# SolenoidX13.net
KiCad netlist of a schematic drawn in EAGLE
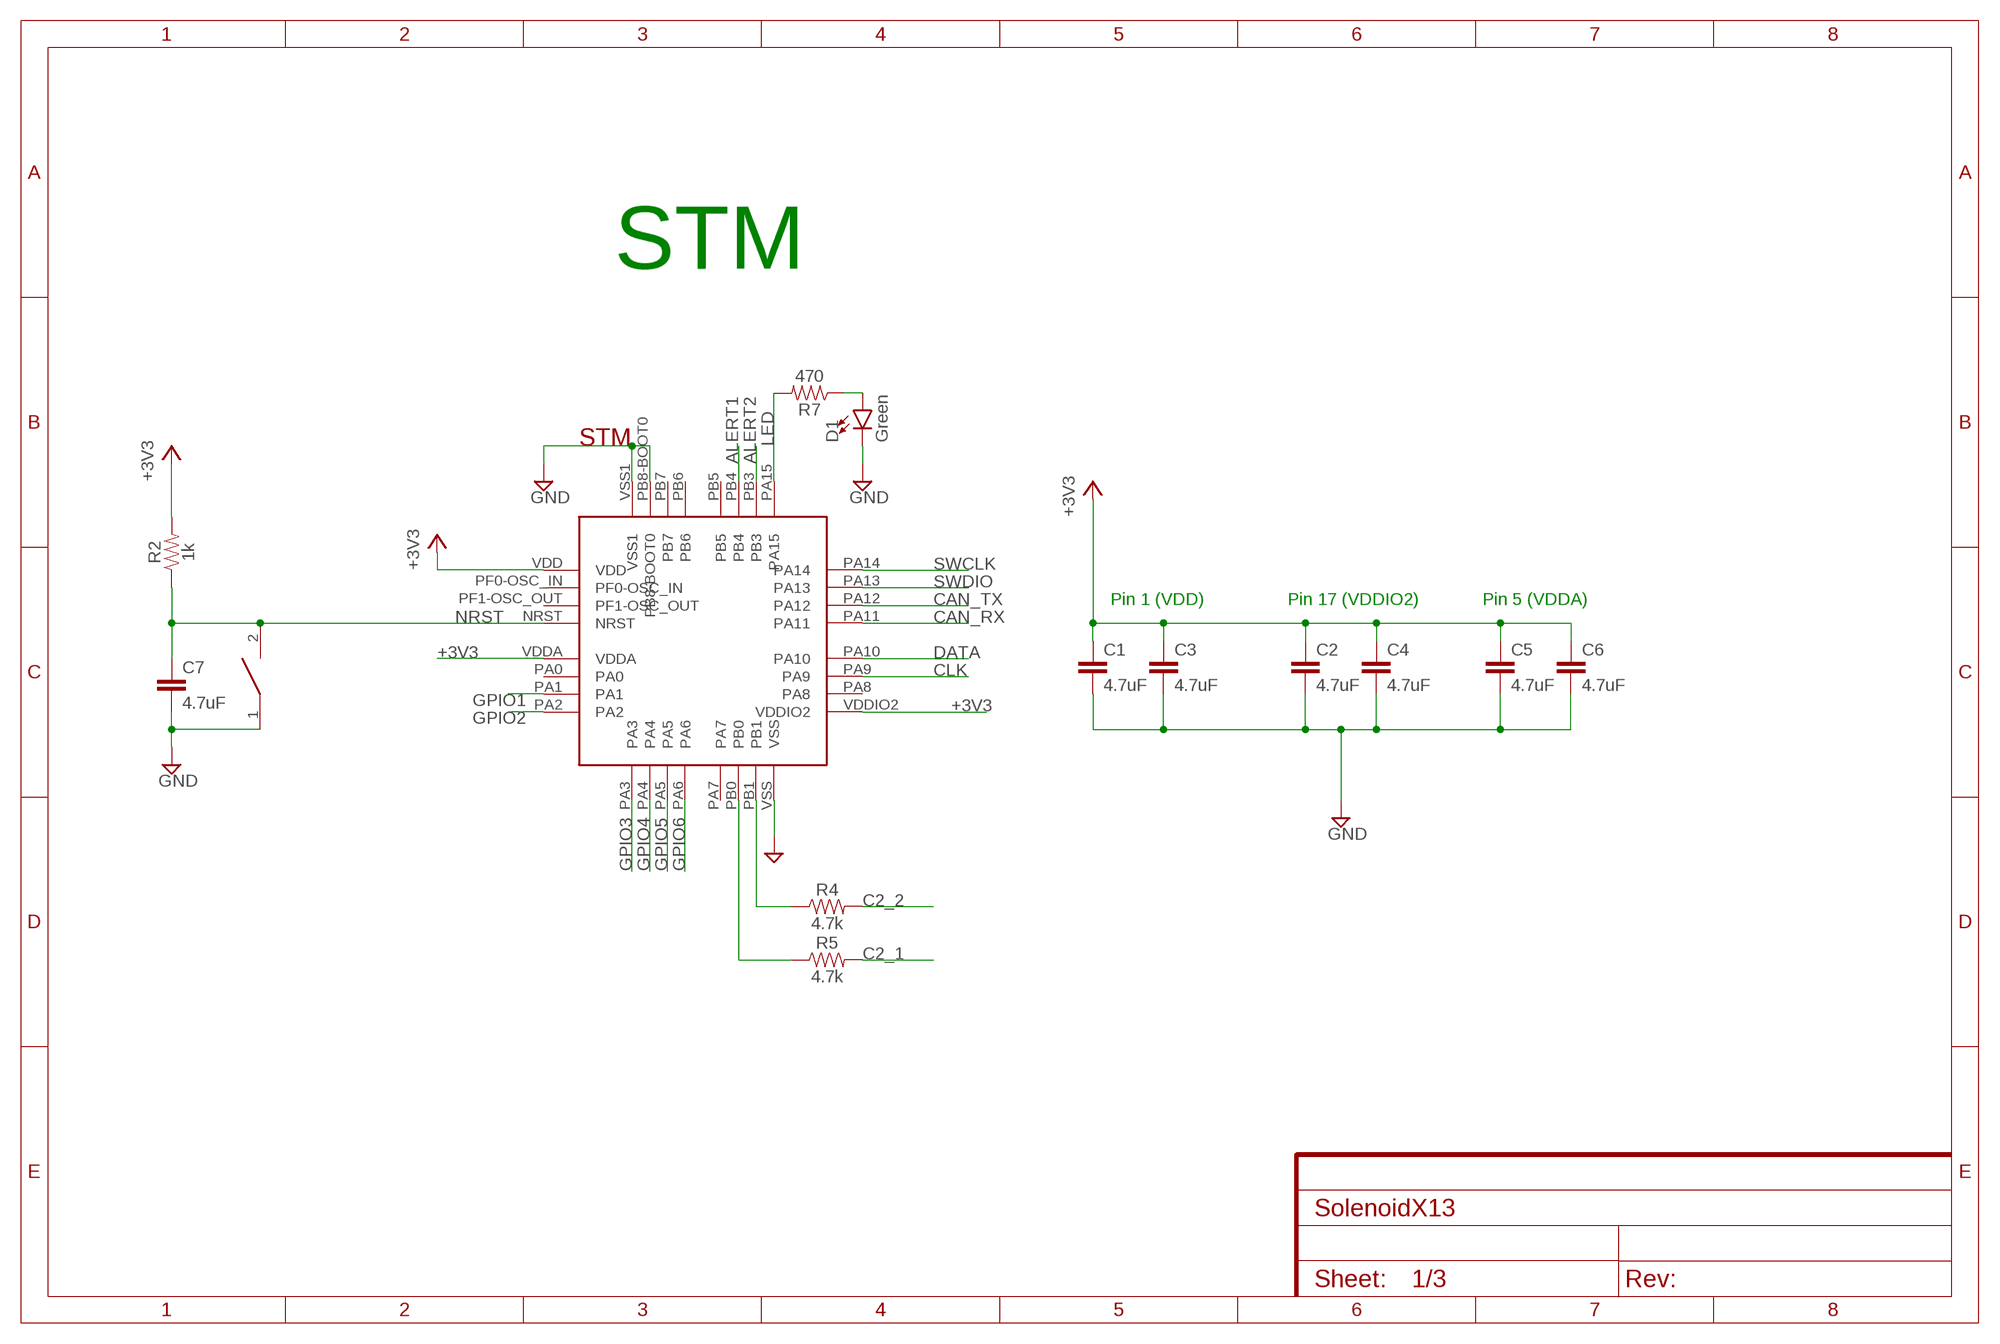
[diagram p0: schematic, sheet 1]
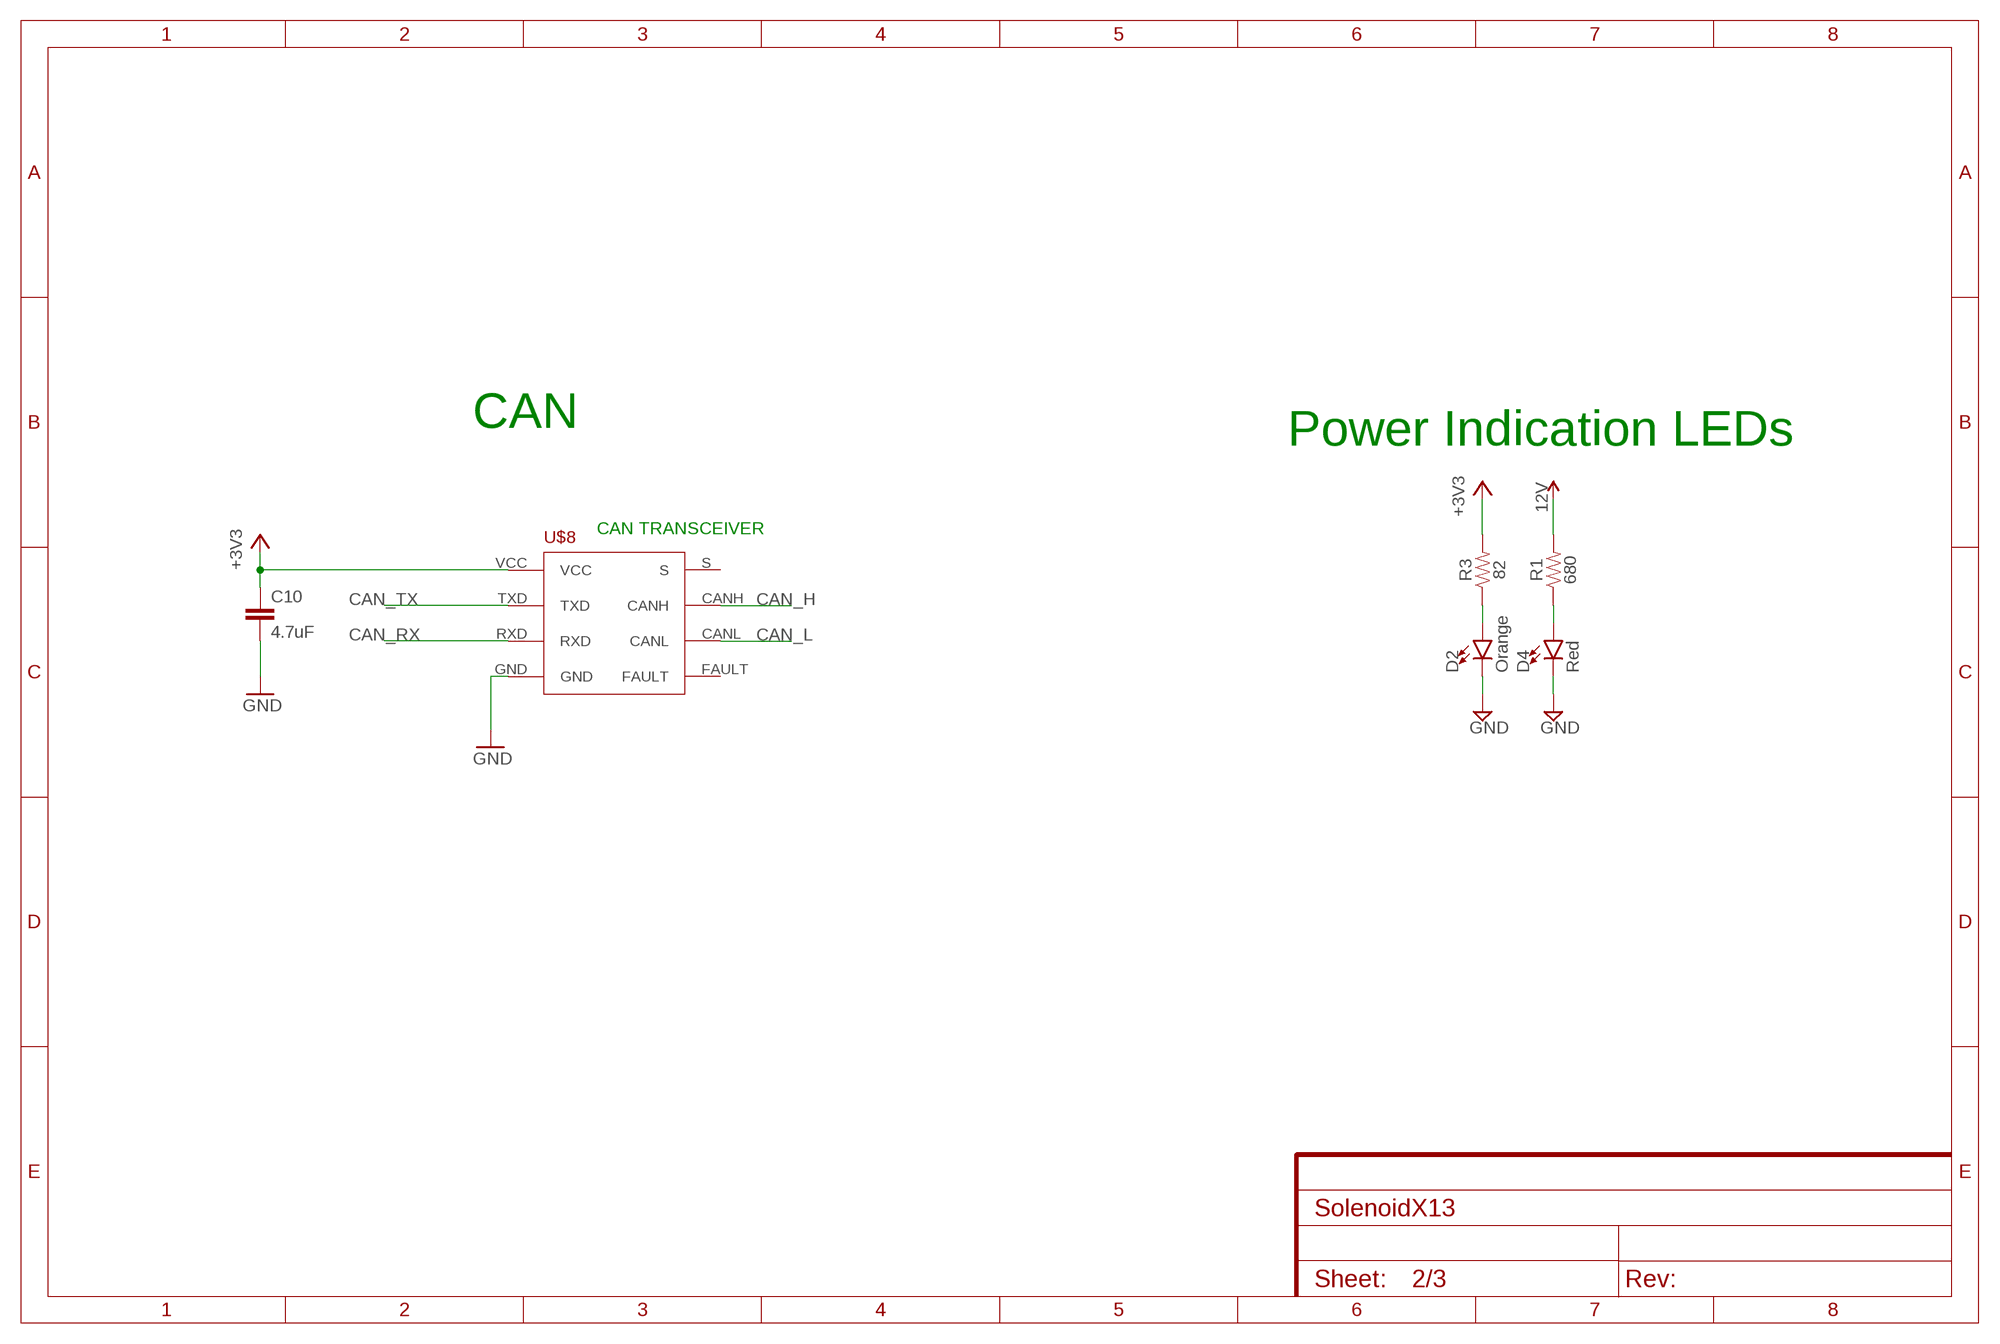
[diagram p1: schematic, sheet 2]
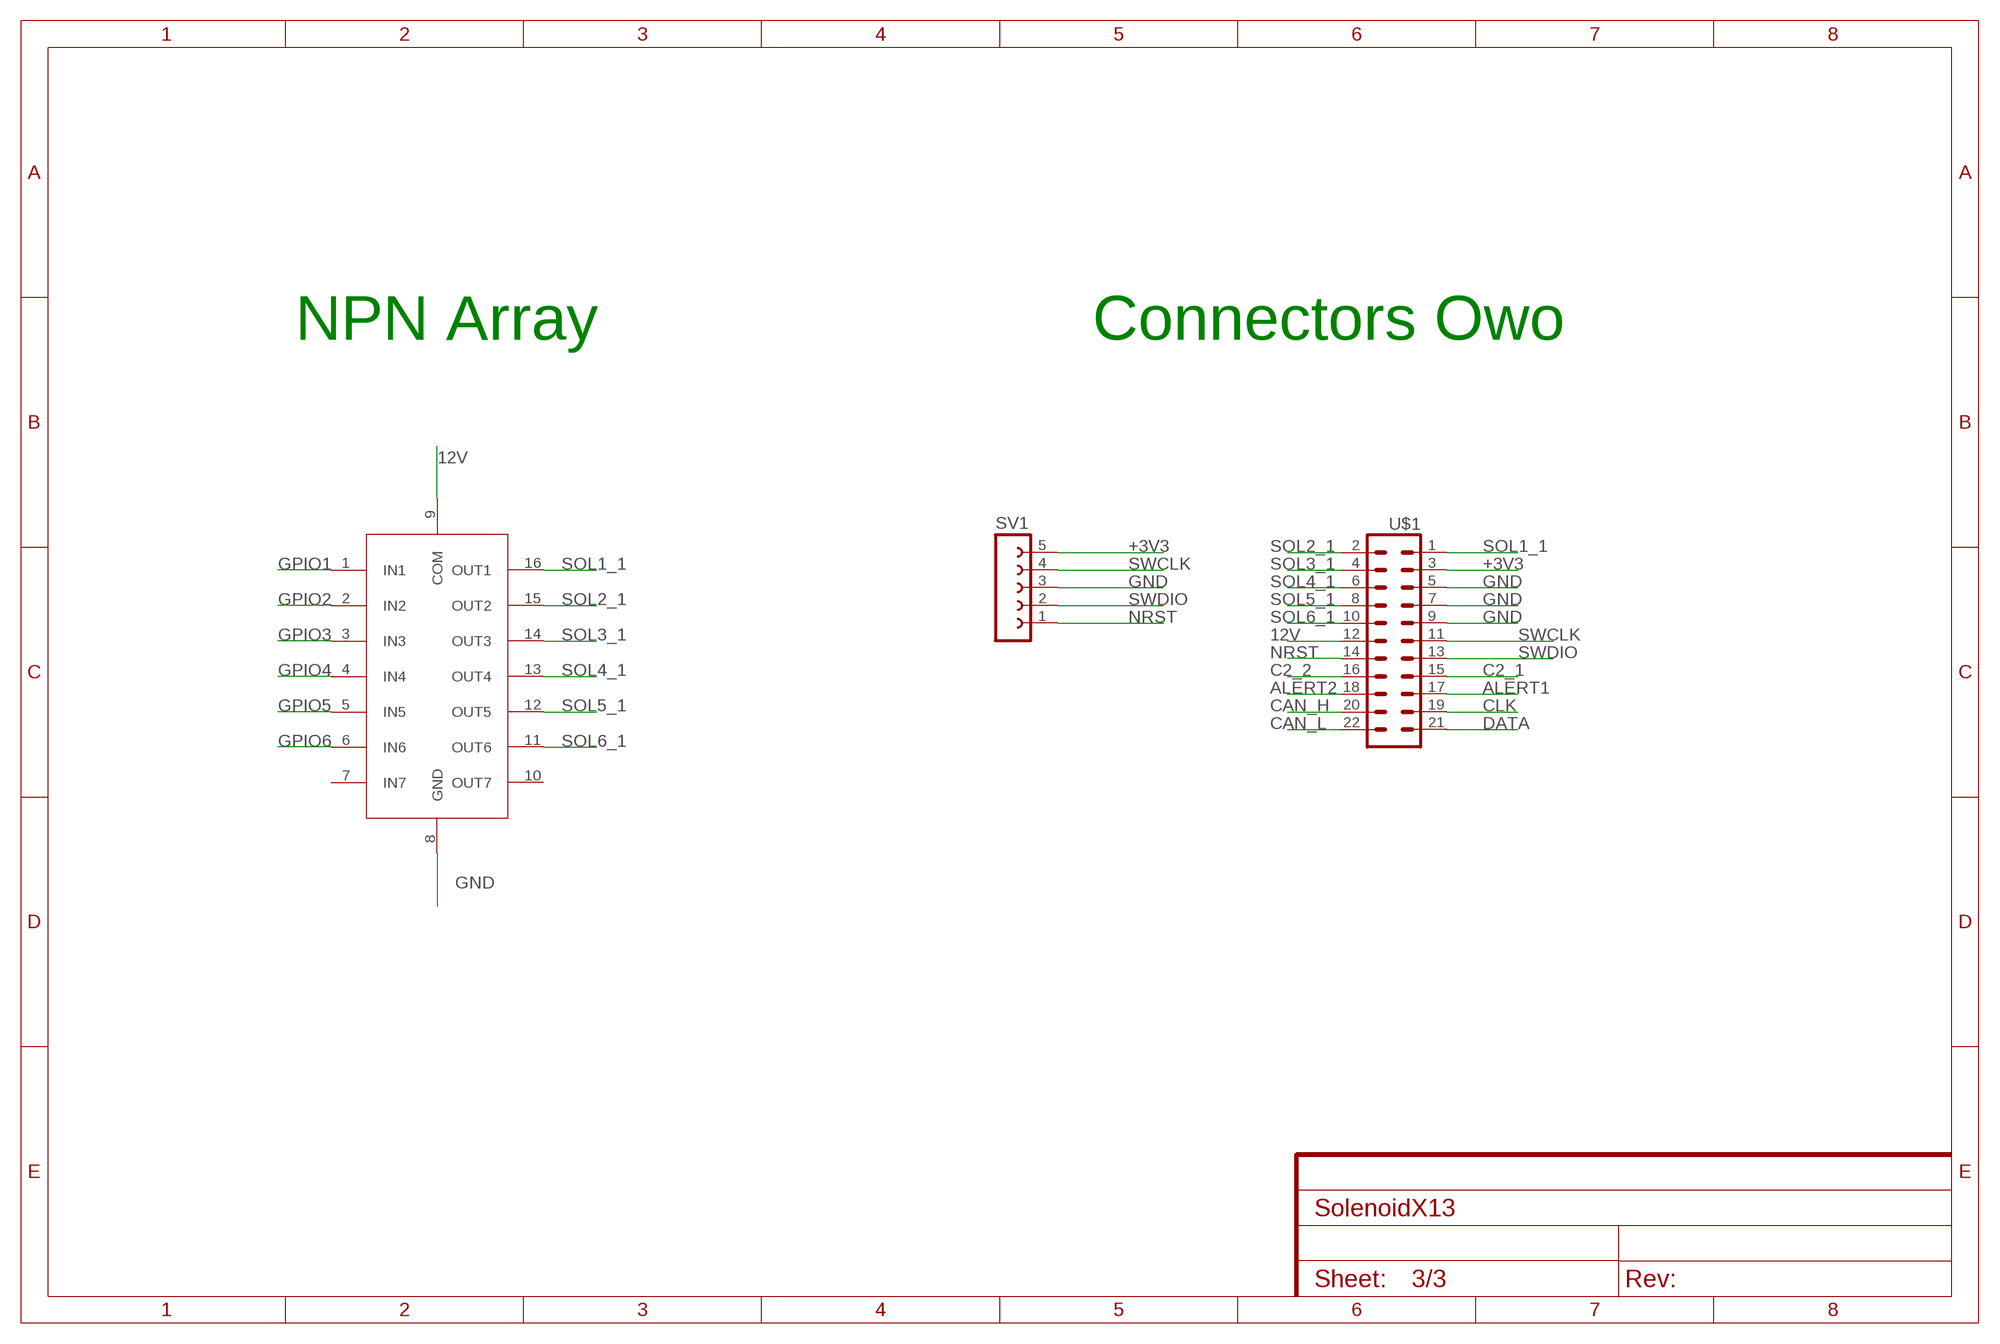
[diagram p2: schematic, sheet 3]

(export (version "E")
  (design (tool "Eeschema 10.0.6"))
  (components
    (comp (ref "C1")
      (value "4.7uF")
      (footprint "eagle-import:0603")
      (libsource (lib "eagle-import") (part "4.7UF0603"))
    )
    (comp (ref "C2")
      (value "4.7uF")
      (footprint "eagle-import:0603")
      (libsource (lib "eagle-import") (part "4.7UF0603"))
    )
    (comp (ref "C3")
      (value "4.7uF")
      (footprint "eagle-import:0603")
      (libsource (lib "eagle-import") (part "4.7UF0603"))
    )
    (comp (ref "C4")
      (value "4.7uF")
      (footprint "eagle-import:0603")
      (libsource (lib "eagle-import") (part "4.7UF0603"))
    )
    (comp (ref "C5")
      (value "4.7uF")
      (footprint "eagle-import:0603")
      (libsource (lib "eagle-import") (part "4.7UF0603"))
    )
    (comp (ref "C6")
      (value "4.7uF")
      (footprint "eagle-import:0603")
      (libsource (lib "eagle-import") (part "4.7UF0603"))
    )
    (comp (ref "C7")
      (value "4.7uF")
      (footprint "eagle-import:0603")
      (libsource (lib "eagle-import") (part "4.7UF0603"))
    )
    (comp (ref "D1")
      (value "Green")
      (footprint "eagle-import:LED-0603")
      (libsource (lib "eagle-import") (part "LED0603"))
    )
    (comp (ref "R2")
      (value "1k")
      (footprint "eagle-import:0603")
      (libsource (lib "eagle-import") (part "1KOHM-0603-1/10W-1%"))
    )
    (comp (ref "R4")
      (value "4.7k")
      (footprint "eagle-import:0603")
      (libsource (lib "eagle-import") (part "4.7KOHM-0603-1/10W-1%"))
    )
    (comp (ref "R5")
      (value "4.7k")
      (footprint "eagle-import:0603")
      (libsource (lib "eagle-import") (part "4.7KOHM-0603-1/10W-1%"))
    )
    (comp (ref "R7")
      (value "470")
      (footprint "eagle-import:0603")
      (libsource (lib "eagle-import") (part "RESISTOR0603"))
    )
    (comp (ref "RESET")
      (value "DISCRETECOMPONENTS_SWITCH")
      (footprint "eagle-import:DISCRETECOMPONENTS_SW_2512")
      (libsource (lib "eagle-import") (part "DISCRETECOMPONENTS_SWITCH"))
    )
    (comp (ref "STM")
      (value "STM32F042K6T6")
      (footprint "eagle-import:STM32F042K6T6")
      (libsource (lib "eagle-import") (part "STM32F042K6T6"))
    )
    (comp (ref "SV1")
      (value "FE05-1")
      (footprint "eagle-import:FE05-1")
      (libsource (lib "eagle-import") (part "FE05-1"))
    )
    (comp (ref "U$1")
      (value "SOL-TO-BKP")
      (footprint "eagle-import:MMS-111-01-DV")
      (libsource (lib "eagle-import") (part "SOL-TO-BKP"))
    )
    (comp (ref "U1")
      (value "ULN2003V12")
      (footprint "eagle-import:ULN2003V12")
      (fields (field (name "MANUFACTURER") "Diodes Inc."))
      (libsource (lib "eagle-import") (part "ULN2003V12"))
    )
    (comp (ref "C10")
      (value "4.7uF")
      (footprint "eagle-import:0603")
      (libsource (lib "eagle-import") (part "4.7UF0603"))
    )
    (comp (ref "D2")
      (value "Orange")
      (footprint "eagle-import:LED-0603")
      (libsource (lib "eagle-import") (part "LED0603"))
    )
    (comp (ref "D4")
      (value "Red")
      (footprint "eagle-import:LED-0603")
      (libsource (lib "eagle-import") (part "LED0603"))
    )
    (comp (ref "R1")
      (value "680")
      (footprint "eagle-import:0603")
      (libsource (lib "eagle-import") (part "680OHM-0603-1/10W-5%"))
    )
    (comp (ref "R3")
      (value "82")
      (footprint "eagle-import:0603")
      (libsource (lib "eagle-import") (part "82OHM-0603-1/10W-1%"))
    )
    (comp (ref "U$8")
      (value "TCAN337D")
      (footprint "eagle-import:TCAN337D")
      (libsource (lib "eagle-import") (part "TCAN337D"))
    )
  )
  (nets
    (net (code "1") (name "+3V3") (class "Default")
      (node (ref "C1") (pin "1") (pinfunction "1_1") (pintype "passive"))
      (node (ref "C10") (pin "1") (pinfunction "1_1") (pintype "passive"))
      (node (ref "C2") (pin "1") (pinfunction "1_1") (pintype "passive"))
      (node (ref "C3") (pin "1") (pinfunction "1_1") (pintype "passive"))
      (node (ref "C4") (pin "1") (pinfunction "1_1") (pintype "passive"))
      (node (ref "C5") (pin "1") (pinfunction "1_1") (pintype "passive"))
      (node (ref "C6") (pin "1") (pinfunction "1_1") (pintype "passive"))
      (node (ref "R2") (pin "2") (pinfunction "2_2") (pintype "passive"))
      (node (ref "R3") (pin "2") (pinfunction "2_2") (pintype "passive"))
      (node (ref "STM") (pin "VDD") (pinfunction "VDD_VDD") (pintype "bidirectional"))
      (node (ref "STM") (pin "VDDA") (pinfunction "VDDA_VDDA") (pintype "bidirectional"))
      (node (ref "STM") (pin "VDDIO2") (pinfunction "VDDIO2_VDDIO2") (pintype "bidirectional"))
      (node (ref "SV1") (pin "5") (pinfunction "5_5") (pintype "passive"))
      (node (ref "U$1") (pin "3") (pinfunction "3_3") (pintype "passive"))
      (node (ref "U$8") (pin "VCC") (pinfunction "VCC_VCC") (pintype "bidirectional"))
    )
    (net (code "2") (name "12V") (class "Default")
      (node (ref "R1") (pin "2") (pinfunction "2_2") (pintype "passive"))
      (node (ref "U$1") (pin "12") (pinfunction "12_12") (pintype "passive"))
      (node (ref "U1") (pin "9") (pinfunction "COM_9") (pintype "bidirectional"))
    )
    (net (code "3") (name "ALERT1") (class "Default")
      (node (ref "STM") (pin "PB4") (pinfunction "PB4_PB4") (pintype "bidirectional"))
      (node (ref "U$1") (pin "17") (pinfunction "17_17") (pintype "passive"))
    )
    (net (code "4") (name "ALERT2") (class "Default")
      (node (ref "STM") (pin "PB3") (pinfunction "PB3_PB3") (pintype "bidirectional"))
      (node (ref "U$1") (pin "18") (pinfunction "18_18") (pintype "passive"))
    )
    (net (code "5") (name "C2_1") (class "Default")
      (node (ref "R5") (pin "2") (pinfunction "2_2") (pintype "passive"))
      (node (ref "U$1") (pin "15") (pinfunction "15_15") (pintype "passive"))
    )
    (net (code "6") (name "C2_2") (class "Default")
      (node (ref "R4") (pin "2") (pinfunction "2_2") (pintype "passive"))
      (node (ref "U$1") (pin "16") (pinfunction "16_16") (pintype "passive"))
    )
    (net (code "7") (name "CAN_H") (class "Default")
      (node (ref "U$1") (pin "20") (pinfunction "20_20") (pintype "passive"))
      (node (ref "U$8") (pin "CANH") (pinfunction "CANH_CANH") (pintype "bidirectional"))
    )
    (net (code "8") (name "CAN_L") (class "Default")
      (node (ref "U$1") (pin "22") (pinfunction "22_22") (pintype "passive"))
      (node (ref "U$8") (pin "CANL") (pinfunction "CANL_CANL") (pintype "bidirectional"))
    )
    (net (code "9") (name "CAN_RX") (class "Default")
      (node (ref "STM") (pin "PA11") (pinfunction "PA11_PA11") (pintype "bidirectional"))
      (node (ref "U$8") (pin "RXD") (pinfunction "RXD_RXD") (pintype "bidirectional"))
    )
    (net (code "10") (name "CAN_TX") (class "Default")
      (node (ref "STM") (pin "PA12") (pinfunction "PA12_PA12") (pintype "bidirectional"))
      (node (ref "U$8") (pin "TXD") (pinfunction "TXD_TXD") (pintype "bidirectional"))
    )
    (net (code "11") (name "CLK") (class "Default")
      (node (ref "STM") (pin "PA9") (pinfunction "PA9_PA9") (pintype "bidirectional"))
      (node (ref "U$1") (pin "19") (pinfunction "19_19") (pintype "passive"))
    )
    (net (code "12") (name "DATA") (class "Default")
      (node (ref "STM") (pin "PA10") (pinfunction "PA10_PA10") (pintype "bidirectional"))
      (node (ref "U$1") (pin "21") (pinfunction "21_21") (pintype "passive"))
    )
    (net (code "13") (name "GND") (class "Default")
      (node (ref "C1") (pin "2") (pinfunction "2_2") (pintype "passive"))
      (node (ref "C10") (pin "2") (pinfunction "2_2") (pintype "passive"))
      (node (ref "C2") (pin "2") (pinfunction "2_2") (pintype "passive"))
      (node (ref "C3") (pin "2") (pinfunction "2_2") (pintype "passive"))
      (node (ref "C4") (pin "2") (pinfunction "2_2") (pintype "passive"))
      (node (ref "C5") (pin "2") (pinfunction "2_2") (pintype "passive"))
      (node (ref "C6") (pin "2") (pinfunction "2_2") (pintype "passive"))
      (node (ref "C7") (pin "2") (pinfunction "2_2") (pintype "passive"))
      (node (ref "D1") (pin "C") (pinfunction "C_C") (pintype "passive"))
      (node (ref "D2") (pin "C") (pinfunction "C_C") (pintype "passive"))
      (node (ref "D4") (pin "C") (pinfunction "C_C") (pintype "passive"))
      (node (ref "RESET") (pin "1") (pinfunction "P$1_1") (pintype "bidirectional"))
      (node (ref "STM") (pin "PB8-BOOT0") (pinfunction "PB8-BOOT0_PB8-BOOT0") (pintype "bidirectional"))
      (node (ref "STM") (pin "VSS") (pinfunction "VSS_VSS") (pintype "bidirectional"))
      (node (ref "STM") (pin "VSS1") (pinfunction "VSS1_VSS1") (pintype "bidirectional"))
      (node (ref "SV1") (pin "3") (pinfunction "3_3") (pintype "passive"))
      (node (ref "U$1") (pin "5") (pinfunction "5_5") (pintype "passive"))
      (node (ref "U$1") (pin "7") (pinfunction "7_7") (pintype "passive"))
      (node (ref "U$1") (pin "9") (pinfunction "9_9") (pintype "passive"))
      (node (ref "U$8") (pin "GND") (pinfunction "GND_GND") (pintype "bidirectional"))
      (node (ref "U1") (pin "8") (pinfunction "GND_8") (pintype "bidirectional"))
    )
    (net (code "14") (name "GPIO1") (class "Default")
      (node (ref "STM") (pin "PA1") (pinfunction "PA1_PA1") (pintype "bidirectional"))
      (node (ref "U1") (pin "1") (pinfunction "IN1_1") (pintype "bidirectional"))
    )
    (net (code "15") (name "GPIO2") (class "Default")
      (node (ref "STM") (pin "PA2") (pinfunction "PA2_PA2") (pintype "bidirectional"))
      (node (ref "U1") (pin "2") (pinfunction "IN2_2") (pintype "bidirectional"))
    )
    (net (code "16") (name "GPIO3") (class "Default")
      (node (ref "STM") (pin "PA3") (pinfunction "PA3_PA3") (pintype "bidirectional"))
      (node (ref "U1") (pin "3") (pinfunction "IN3_3") (pintype "bidirectional"))
    )
    (net (code "17") (name "GPIO4") (class "Default")
      (node (ref "STM") (pin "PA4") (pinfunction "PA4_PA4") (pintype "bidirectional"))
      (node (ref "U1") (pin "4") (pinfunction "IN4_4") (pintype "bidirectional"))
    )
    (net (code "18") (name "GPIO5") (class "Default")
      (node (ref "STM") (pin "PA5") (pinfunction "PA5_PA5") (pintype "bidirectional"))
      (node (ref "U1") (pin "5") (pinfunction "IN5_5") (pintype "bidirectional"))
    )
    (net (code "19") (name "GPIO6") (class "Default")
      (node (ref "STM") (pin "PA6") (pinfunction "PA6_PA6") (pintype "bidirectional"))
      (node (ref "U1") (pin "6") (pinfunction "IN6_6") (pintype "bidirectional"))
    )
    (net (code "20") (name "LED") (class "Default")
      (node (ref "R7") (pin "2") (pinfunction "2_2") (pintype "passive"))
      (node (ref "STM") (pin "PA15") (pinfunction "PA15_PA15") (pintype "bidirectional"))
    )
    (net (code "21") (name "NRST") (class "Default")
      (node (ref "C7") (pin "1") (pinfunction "1_1") (pintype "passive"))
      (node (ref "R2") (pin "1") (pinfunction "1_1") (pintype "passive"))
      (node (ref "RESET") (pin "2") (pinfunction "P$2_2") (pintype "bidirectional"))
      (node (ref "STM") (pin "NRST") (pinfunction "NRST_NRST") (pintype "bidirectional"))
      (node (ref "SV1") (pin "1") (pinfunction "1_1") (pintype "passive"))
      (node (ref "U$1") (pin "14") (pinfunction "14_14") (pintype "passive"))
    )
    (net (code "22") (name "Net-(D1-PadA)") (class "Default")
      (node (ref "D1") (pin "A") (pinfunction "A_A") (pintype "passive"))
      (node (ref "R7") (pin "1") (pinfunction "1_1") (pintype "passive"))
    )
    (net (code "23") (name "Net-(D2-PadA)") (class "Default")
      (node (ref "D2") (pin "A") (pinfunction "A_A") (pintype "passive"))
      (node (ref "R3") (pin "1") (pinfunction "1_1") (pintype "passive"))
    )
    (net (code "24") (name "Net-(D4-PadA)") (class "Default")
      (node (ref "D4") (pin "A") (pinfunction "A_A") (pintype "passive"))
      (node (ref "R1") (pin "1") (pinfunction "1_1") (pintype "passive"))
    )
    (net (code "25") (name "Net-(R4-Pad1)") (class "Default")
      (node (ref "R4") (pin "1") (pinfunction "1_1") (pintype "passive"))
      (node (ref "STM") (pin "PB1") (pinfunction "PB1_PB1") (pintype "bidirectional"))
    )
    (net (code "26") (name "Net-(R5-Pad1)") (class "Default")
      (node (ref "R5") (pin "1") (pinfunction "1_1") (pintype "passive"))
      (node (ref "STM") (pin "PB0") (pinfunction "PB0_PB0") (pintype "bidirectional"))
    )
    (net (code "27") (name "SOL1_1") (class "Default")
      (node (ref "U$1") (pin "1") (pinfunction "1_1") (pintype "passive"))
      (node (ref "U1") (pin "16") (pinfunction "OUT1_16") (pintype "bidirectional"))
    )
    (net (code "28") (name "SOL2_1") (class "Default")
      (node (ref "U$1") (pin "2") (pinfunction "2_2") (pintype "passive"))
      (node (ref "U1") (pin "15") (pinfunction "OUT2_15") (pintype "bidirectional"))
    )
    (net (code "29") (name "SOL3_1") (class "Default")
      (node (ref "U$1") (pin "4") (pinfunction "4_4") (pintype "passive"))
      (node (ref "U1") (pin "14") (pinfunction "OUT3_14") (pintype "bidirectional"))
    )
    (net (code "30") (name "SOL4_1") (class "Default")
      (node (ref "U$1") (pin "6") (pinfunction "6_6") (pintype "passive"))
      (node (ref "U1") (pin "13") (pinfunction "OUT4_13") (pintype "bidirectional"))
    )
    (net (code "31") (name "SOL5_1") (class "Default")
      (node (ref "U$1") (pin "8") (pinfunction "8_8") (pintype "passive"))
      (node (ref "U1") (pin "12") (pinfunction "OUT5_12") (pintype "bidirectional"))
    )
    (net (code "32") (name "SOL6_1") (class "Default")
      (node (ref "U$1") (pin "10") (pinfunction "10_10") (pintype "passive"))
      (node (ref "U1") (pin "11") (pinfunction "OUT6_11") (pintype "bidirectional"))
    )
    (net (code "33") (name "SWCLK") (class "Default")
      (node (ref "STM") (pin "PA14") (pinfunction "PA14_PA14") (pintype "bidirectional"))
      (node (ref "SV1") (pin "4") (pinfunction "4_4") (pintype "passive"))
      (node (ref "U$1") (pin "11") (pinfunction "11_11") (pintype "passive"))
    )
    (net (code "34") (name "SWDIO") (class "Default")
      (node (ref "STM") (pin "PA13") (pinfunction "PA13_PA13") (pintype "bidirectional"))
      (node (ref "SV1") (pin "2") (pinfunction "2_2") (pintype "passive"))
      (node (ref "U$1") (pin "13") (pinfunction "13_13") (pintype "passive"))
    )
    (net (code "35") (name "unconnected-(STM-PadPA0)") (class "Default")
      (node (ref "STM") (pin "PA0") (pinfunction "PA0_PA0") (pintype "bidirectional"))
    )
    (net (code "36") (name "unconnected-(STM-PadPA7)") (class "Default")
      (node (ref "STM") (pin "PA7") (pinfunction "PA7_PA7") (pintype "bidirectional"))
    )
    (net (code "37") (name "unconnected-(STM-PadPA8)") (class "Default")
      (node (ref "STM") (pin "PA8") (pinfunction "PA8_PA8") (pintype "bidirectional"))
    )
    (net (code "38") (name "unconnected-(STM-PadPB5)") (class "Default")
      (node (ref "STM") (pin "PB5") (pinfunction "PB5_PB5") (pintype "bidirectional"))
    )
    (net (code "39") (name "unconnected-(STM-PadPB6)") (class "Default")
      (node (ref "STM") (pin "PB6") (pinfunction "PB6_PB6") (pintype "bidirectional"))
    )
    (net (code "40") (name "unconnected-(STM-PadPB7)") (class "Default")
      (node (ref "STM") (pin "PB7") (pinfunction "PB7_PB7") (pintype "bidirectional"))
    )
    (net (code "41") (name "unconnected-(STM-PadPF0-OSC_IN)") (class "Default")
      (node (ref "STM") (pin "PF0-OSC_IN") (pinfunction "PF0-OSC_IN_PF0-OSC_IN") (pintype "bidirectional"))
    )
    (net (code "42") (name "unconnected-(STM-PadPF1-OSC_OUT)") (class "Default")
      (node (ref "STM") (pin "PF1-OSC_OUT") (pinfunction "PF1-OSC_OUT_PF1-OSC_OUT") (pintype "bidirectional"))
    )
    (net (code "43") (name "unconnected-(U$8-PadFAULT)") (class "Default")
      (node (ref "U$8") (pin "FAULT") (pinfunction "FAULT_FAULT") (pintype "bidirectional"))
    )
    (net (code "44") (name "unconnected-(U$8-PadS)") (class "Default")
      (node (ref "U$8") (pin "S") (pinfunction "S_S") (pintype "bidirectional"))
    )
    (net (code "45") (name "unconnected-(U1-IN7-Pad7)") (class "Default")
      (node (ref "U1") (pin "7") (pinfunction "IN7_7") (pintype "bidirectional"))
    )
    (net (code "46") (name "unconnected-(U1-OUT7-Pad10)") (class "Default")
      (node (ref "U1") (pin "10") (pinfunction "OUT7_10") (pintype "bidirectional"))
    )
  )
)
